# 04_DISPLAY.net
KiCad netlist of a schematic drawn in Altium Designer
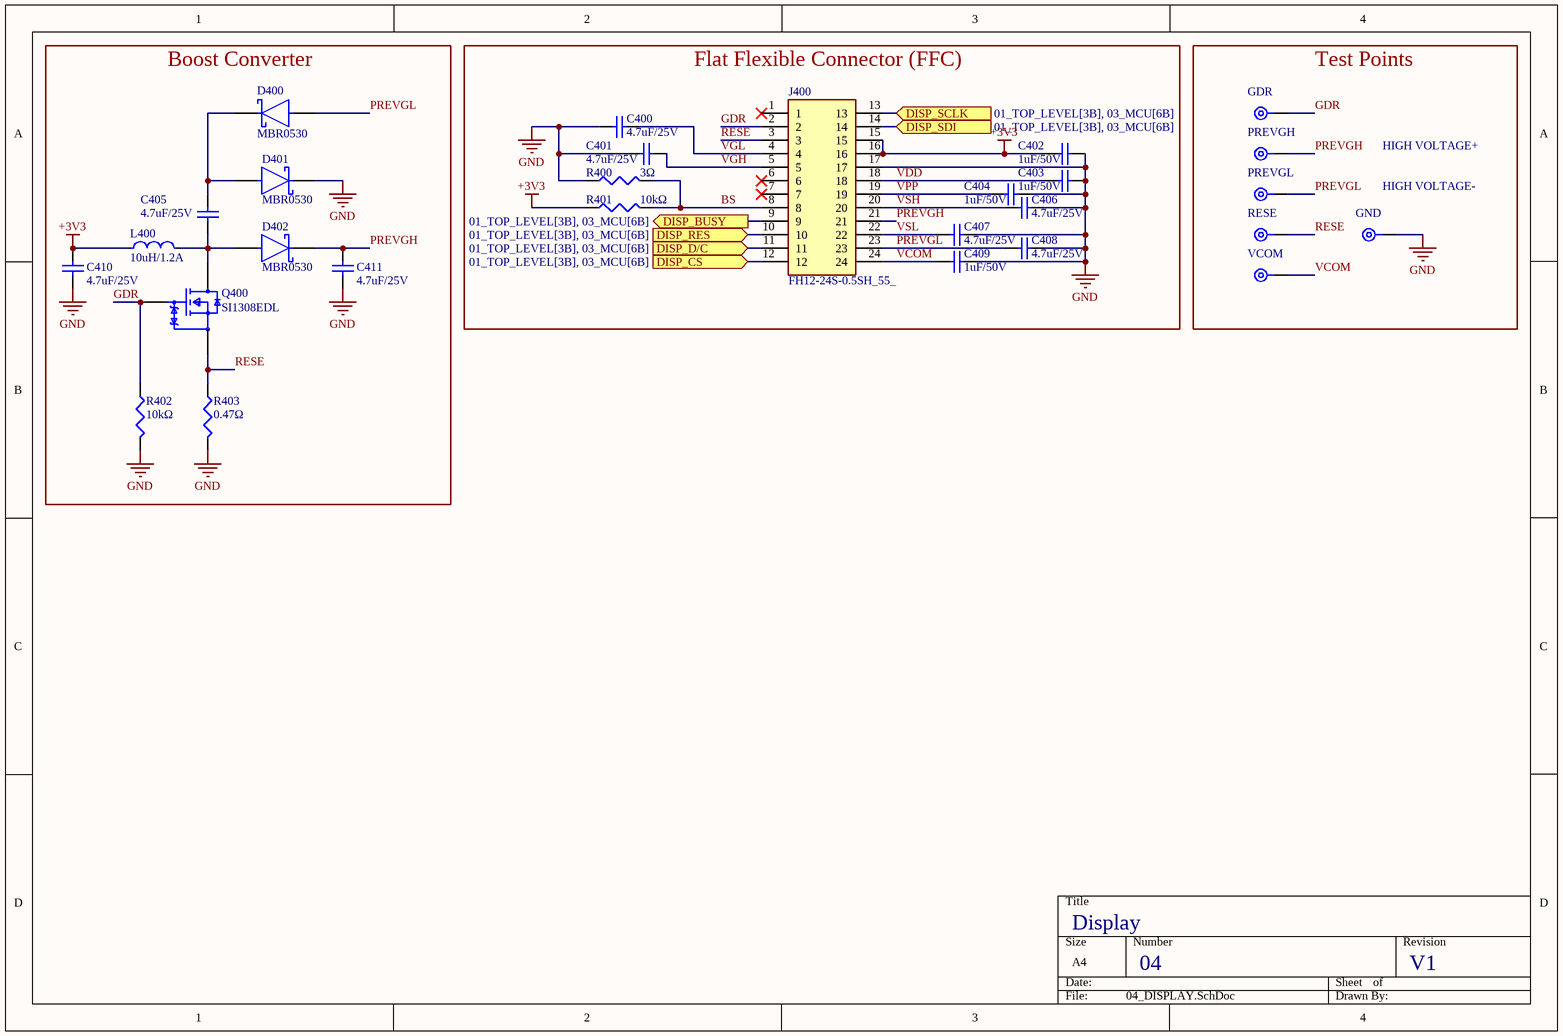
[diagram p0: 04_DISPLAY.SchDoc]

(export (version "E")
  (design (tool "Eeschema 10.0.6"))
  (components
    (comp (ref "C400")
      (value "4.7uF/25V")
      (footprint "CAPC1005X55X25LL05T10")
      (description "Chip Capacitor, 1 uF, +/- 10%, 6.3 V, 0402 (1005 Metric)")
      (fields (field (name "TOLERANCE") "10%") (field (name "Comment") "Capacitor 1 uF +/- 10% 6.3 V 0402"))
      (libsource (lib "CPRT Workspace") (part "CAP-NP-2"))
    )
    (comp (ref "C401")
      (value "4.7uF/25V")
      (footprint "CAPC1005X55X25LL05T10")
      (description "Chip Capacitor, 1 uF, +/- 10%, 6.3 V, 0402 (1005 Metric)")
      (fields (field (name "TOLERANCE") "10%") (field (name "Comment") "Capacitor 1 uF +/- 10% 6.3 V 0402"))
      (libsource (lib "CPRT Workspace") (part "CAP-NP-2"))
    )
    (comp (ref "C402")
      (value "1uF/50V")
      (footprint "CAPC1005X55X25LL05T10")
      (description "Chip Capacitor, 1 uF, +/- 10%, 6.3 V, 0402 (1005 Metric)")
      (fields (field (name "TOLERANCE") "10%") (field (name "Comment") "Capacitor 1 uF +/- 10% 6.3 V 0402"))
      (libsource (lib "CPRT Workspace") (part "CAP-NP-2"))
    )
    (comp (ref "C403")
      (value "1uF/50V")
      (footprint "CAPC1005X55X25LL05T10")
      (description "Chip Capacitor, 1 uF, +/- 10%, 6.3 V, 0402 (1005 Metric)")
      (fields (field (name "TOLERANCE") "10%") (field (name "Comment") "Capacitor 1 uF +/- 10% 6.3 V 0402"))
      (libsource (lib "CPRT Workspace") (part "CAP-NP-2"))
    )
    (comp (ref "C404")
      (value "1uF/50V")
      (footprint "CAPC1005X55X25LL05T10")
      (description "Chip Capacitor, 1 uF, +/- 10%, 6.3 V, 0402 (1005 Metric)")
      (fields (field (name "TOLERANCE") "10%") (field (name "Comment") "Capacitor 1 uF +/- 10% 6.3 V 0402"))
      (libsource (lib "CPRT Workspace") (part "CAP-NP-2"))
    )
    (comp (ref "C405")
      (value "4.7uF/25V")
      (footprint "CAPC1005X55X25LL05T10")
      (description "Chip Capacitor, 1 uF, +/- 10%, 6.3 V, 0402 (1005 Metric)")
      (fields (field (name "TOLERANCE") "10%") (field (name "Comment") "Capacitor 1 uF +/- 10% 6.3 V 0402"))
      (libsource (lib "CPRT Workspace") (part "CAP-NP-2"))
    )
    (comp (ref "C406")
      (value "4.7uF/25V")
      (footprint "CAPC1005X55X25LL05T10")
      (description "Chip Capacitor, 1 uF, +/- 10%, 6.3 V, 0402 (1005 Metric)")
      (fields (field (name "TOLERANCE") "10%") (field (name "Comment") "Capacitor 1 uF +/- 10% 6.3 V 0402"))
      (libsource (lib "CPRT Workspace") (part "CAP-NP-2"))
    )
    (comp (ref "C407")
      (value "4.7uF/25V")
      (footprint "CAPC1005X55X25LL05T10")
      (description "Chip Capacitor, 1 uF, +/- 10%, 6.3 V, 0402 (1005 Metric)")
      (fields (field (name "TOLERANCE") "10%") (field (name "Comment") "Capacitor 1 uF +/- 10% 6.3 V 0402"))
      (libsource (lib "CPRT Workspace") (part "CAP-NP-2"))
    )
    (comp (ref "C408")
      (value "4.7uF/25V")
      (footprint "CAPC1005X55X25LL05T10")
      (description "Chip Capacitor, 1 uF, +/- 10%, 6.3 V, 0402 (1005 Metric)")
      (fields (field (name "TOLERANCE") "10%") (field (name "Comment") "Capacitor 1 uF +/- 10% 6.3 V 0402"))
      (libsource (lib "CPRT Workspace") (part "CAP-NP-2"))
    )
    (comp (ref "C409")
      (value "1uF/50V")
      (footprint "CAPC1005X55X25LL05T10")
      (description "Chip Capacitor, 1 uF, +/- 10%, 6.3 V, 0402 (1005 Metric)")
      (fields (field (name "TOLERANCE") "10%") (field (name "Comment") "Capacitor 1 uF +/- 10% 6.3 V 0402"))
      (libsource (lib "CPRT Workspace") (part "CAP-NP-2"))
    )
    (comp (ref "C410")
      (value "4.7uF/25V")
      (footprint "CAPC1005X55X25LL05T10")
      (description "Chip Capacitor, 1 uF, +/- 10%, 6.3 V, 0402 (1005 Metric)")
      (fields (field (name "TOLERANCE") "10%") (field (name "Comment") "Capacitor 1 uF +/- 10% 6.3 V 0402"))
      (libsource (lib "CPRT Workspace") (part "CAP-NP-2"))
    )
    (comp (ref "C411")
      (value "4.7uF/25V")
      (footprint "CAPC1005X55X25LL05T10")
      (description "Chip Capacitor, 1 uF, +/- 10%, 6.3 V, 0402 (1005 Metric)")
      (fields (field (name "TOLERANCE") "10%") (field (name "Comment") "Capacitor 1 uF +/- 10% 6.3 V 0402"))
      (libsource (lib "CPRT Workspace") (part "CAP-NP-2"))
    )
    (comp (ref "D400")
      (value "MBR0530")
      (footprint "FP-425-04-MFG")
      (description "DIODE SCHOTTKY 30V 500MA SOD123")
      (libsource (lib "Altium Content Vault") (part "1d6ec82d83fb6aee721767c19dac4b9"))
    )
    (comp (ref "D401")
      (value "MBR0530")
      (footprint "FP-425-04-MFG")
      (description "DIODE SCHOTTKY 30V 500MA SOD123")
      (libsource (lib "Altium Content Vault") (part "1d6ec82d83fb6aee721767c19dac4b9"))
    )
    (comp (ref "D402")
      (value "MBR0530")
      (footprint "FP-425-04-MFG")
      (description "DIODE SCHOTTKY 30V 500MA SOD123")
      (libsource (lib "Altium Content Vault") (part "1d6ec82d83fb6aee721767c19dac4b9"))
    )
    (comp (ref "GDR")
      (value "TPAD10R")
      (footprint "TEST_POINT")
      (description "Testpont Pad 10R")
      (libsource (lib "Schlib1") (part "TEST_POINT"))
    )
    (comp (ref "GND")
      (value "TPAD10R")
      (footprint "TEST_POINT")
      (description "Testpont Pad 10R")
      (libsource (lib "Schlib1") (part "TEST_POINT"))
    )
    (comp (ref "J400")
      (value "FH12-24S-0.5SH_55_")
      (footprint "FH12-24S-0.5SH(55)")
      (description "Connector")
      (fields
        (field (name "MANUFACTURER_PART_NUMBER") "FH12-24S-0.5SH(55)")
        (field (name "MOUSER PART NUMBER") "798-FH12-24S-0.5SH55")
      )
      (libsource (lib "Schlib1") (part "FH12-24S-0.5SH_55_"))
    )
    (comp (ref "L400")
      (value "10uH/1.2A")
      (footprint "FP-LQH5BPB_T0-MFG")
      (description "Wire Wound Ferrite Inductor for Power Lines 10μH ±20% 0.1272Ω 1.60A 2020")
      (fields (field (name "TOLERANCE") "20%"))
      (libsource (lib "Altium Content Vault") (part "725321dda6339637d4d059423bc1c3c"))
    )
    (comp (ref "PREVGH")
      (value "TPAD10R")
      (footprint "TEST_POINT")
      (description "Testpont Pad 10R")
      (libsource (lib "Schlib1") (part "TEST_POINT"))
    )
    (comp (ref "PREVGL")
      (value "TPAD10R")
      (footprint "TEST_POINT")
      (description "Testpont Pad 10R")
      (libsource (lib "Schlib1") (part "TEST_POINT"))
    )
    (comp (ref "Q400")
      (value "SI1308EDL")
      (footprint "FP-5549-MFG")
      (description "MOSFET N-CH 30V 1.4A SC-70-3")
      (libsource (lib "Altium Content Vault") (part "e96677422f20f20903245877d22b385"))
    )
    (comp (ref "R400")
      (value "3Ω")
      (footprint "RESC0402(1005)_L")
      (description "100R 0.063W 1% 0402 (1005 Metric)  SMD")
      (fields (field (name "TOLERANCE") "1%") (field (name "POWER") "63mW"))
      (libsource (lib "CPRT Workspace") (part "100R2F"))
    )
    (comp (ref "R401")
      (value "10kΩ")
      (footprint "RESC0402(1005)_L")
      (description "100R 0.063W 1% 0402 (1005 Metric)  SMD")
      (fields (field (name "TOLERANCE") "1%") (field (name "POWER") "63mW"))
      (libsource (lib "CPRT Workspace") (part "100R2F"))
    )
    (comp (ref "R402")
      (value "10kΩ")
      (footprint "RESC0402(1005)_L")
      (description "100R 0.063W 1% 0402 (1005 Metric)  SMD")
      (fields (field (name "TOLERANCE") "1%") (field (name "POWER") "63mW"))
      (libsource (lib "CPRT Workspace") (part "100R2F"))
    )
    (comp (ref "R403")
      (value "0.47Ω")
      (footprint "RESC0402(1005)_L")
      (description "100R 0.063W 1% 0402 (1005 Metric)  SMD")
      (fields (field (name "TOLERANCE") "1%") (field (name "POWER") "63mW"))
      (libsource (lib "CPRT Workspace") (part "100R2F"))
    )
    (comp (ref "RESE")
      (value "TPAD10R")
      (footprint "TEST_POINT")
      (description "Testpont Pad 10R")
      (libsource (lib "Schlib1") (part "TEST_POINT"))
    )
    (comp (ref "VCOM")
      (value "TPAD10R")
      (footprint "TEST_POINT")
      (description "Testpont Pad 10R")
      (libsource (lib "Schlib1") (part "TEST_POINT"))
    )
  )
  (nets
    (net (code "1") (name "+3V3") (class "Default")
      (node (ref "C402") (pin "2") (pinfunction "2_2") (pintype "passive"))
      (node (ref "C410") (pin "2") (pinfunction "2_2") (pintype "passive"))
      (node (ref "J400") (pin "15") (pinfunction "15_15") (pintype "passive"))
      (node (ref "J400") (pin "16") (pinfunction "16_16") (pintype "passive"))
      (node (ref "L400") (pin "1") (pinfunction "1_1") (pintype "passive"))
      (node (ref "R401") (pin "1") (pinfunction "1_1") (pintype "passive"))
    )
    (net (code "2") (name "/BS") (class "Default")
      (node (ref "J400") (pin "8") (pinfunction "8_8") (pintype "passive"))
      (node (ref "R400") (pin "2") (pinfunction "2_2") (pintype "passive"))
      (node (ref "R401") (pin "2") (pinfunction "2_2") (pintype "passive"))
    )
    (net (code "3") (name "/DISP_BUSY") (class "Default")
      (node (ref "J400") (pin "9") (pinfunction "9_9") (pintype "passive"))
    )
    (net (code "4") (name "/DISP_CS") (class "Default")
      (node (ref "J400") (pin "12") (pinfunction "12_12") (pintype "passive"))
    )
    (net (code "5") (name "/DISP_D{slash}C") (class "Default")
      (node (ref "J400") (pin "11") (pinfunction "11_11") (pintype "passive"))
    )
    (net (code "6") (name "/DISP_RES") (class "Default")
      (node (ref "J400") (pin "10") (pinfunction "10_10") (pintype "passive"))
    )
    (net (code "7") (name "/DISP_SCLK") (class "Default")
      (node (ref "J400") (pin "13") (pinfunction "13_13") (pintype "passive"))
    )
    (net (code "8") (name "/DISP_SDI") (class "Default")
      (node (ref "J400") (pin "14") (pinfunction "14_14") (pintype "passive"))
    )
    (net (code "9") (name "/GDR") (class "Default")
      (node (ref "GDR") (pin "1") (pinfunction "1_1") (pintype "passive"))
      (node (ref "J400") (pin "2") (pinfunction "2_2") (pintype "passive"))
      (node (ref "Q400") (pin "1") (pinfunction "G_1") (pintype "passive"))
      (node (ref "R402") (pin "1") (pinfunction "1_1") (pintype "passive"))
    )
    (net (code "10") (name "/PREVGH") (class "Default")
      (node (ref "C411") (pin "2") (pinfunction "2_2") (pintype "passive"))
      (node (ref "D402") (pin "1") (pinfunction "C_1") (pintype "passive"))
      (node (ref "J400") (pin "21") (pinfunction "21_21") (pintype "passive"))
      (node (ref "PREVGH") (pin "1") (pinfunction "1_1") (pintype "passive"))
    )
    (net (code "11") (name "/PREVGL") (class "Default")
      (node (ref "C408") (pin "2") (pinfunction "2_2") (pintype "passive"))
      (node (ref "D400") (pin "2") (pinfunction "A_2") (pintype "passive"))
      (node (ref "J400") (pin "23") (pinfunction "23_23") (pintype "passive"))
      (node (ref "PREVGL") (pin "1") (pinfunction "1_1") (pintype "passive"))
    )
    (net (code "12") (name "/RESE") (class "Default")
      (node (ref "J400") (pin "3") (pinfunction "3_3") (pintype "passive"))
      (node (ref "Q400") (pin "2") (pinfunction "S_2") (pintype "passive"))
      (node (ref "R403") (pin "1") (pinfunction "1_1") (pintype "passive"))
      (node (ref "RESE") (pin "1") (pinfunction "1_1") (pintype "passive"))
    )
    (net (code "13") (name "/VCOM") (class "Default")
      (node (ref "C409") (pin "2") (pinfunction "2_2") (pintype "passive"))
      (node (ref "J400") (pin "24") (pinfunction "24_24") (pintype "passive"))
      (node (ref "VCOM") (pin "1") (pinfunction "1_1") (pintype "passive"))
    )
    (net (code "14") (name "/VDD") (class "Default")
      (node (ref "C403") (pin "2") (pinfunction "2_2") (pintype "passive"))
      (node (ref "J400") (pin "18") (pinfunction "18_18") (pintype "passive"))
    )
    (net (code "15") (name "/VGH") (class "Default")
      (node (ref "C401") (pin "1") (pinfunction "1_1") (pintype "passive"))
      (node (ref "J400") (pin "5") (pinfunction "5_5") (pintype "passive"))
    )
    (net (code "16") (name "/VGL") (class "Default")
      (node (ref "C400") (pin "1") (pinfunction "1_1") (pintype "passive"))
      (node (ref "J400") (pin "4") (pinfunction "4_4") (pintype "passive"))
    )
    (net (code "17") (name "/VPP") (class "Default")
      (node (ref "C404") (pin "2") (pinfunction "2_2") (pintype "passive"))
      (node (ref "J400") (pin "19") (pinfunction "19_19") (pintype "passive"))
    )
    (net (code "18") (name "/VSH") (class "Default")
      (node (ref "C406") (pin "2") (pinfunction "2_2") (pintype "passive"))
      (node (ref "J400") (pin "20") (pinfunction "20_20") (pintype "passive"))
    )
    (net (code "19") (name "/VSL") (class "Default")
      (node (ref "C407") (pin "2") (pinfunction "2_2") (pintype "passive"))
      (node (ref "J400") (pin "22") (pinfunction "22_22") (pintype "passive"))
    )
    (net (code "20") (name "GND") (class "Default")
      (node (ref "C400") (pin "2") (pinfunction "2_2") (pintype "passive"))
      (node (ref "C401") (pin "2") (pinfunction "2_2") (pintype "passive"))
      (node (ref "C402") (pin "1") (pinfunction "1_1") (pintype "passive"))
      (node (ref "C403") (pin "1") (pinfunction "1_1") (pintype "passive"))
      (node (ref "C404") (pin "1") (pinfunction "1_1") (pintype "passive"))
      (node (ref "C406") (pin "1") (pinfunction "1_1") (pintype "passive"))
      (node (ref "C407") (pin "1") (pinfunction "1_1") (pintype "passive"))
      (node (ref "C408") (pin "1") (pinfunction "1_1") (pintype "passive"))
      (node (ref "C409") (pin "1") (pinfunction "1_1") (pintype "passive"))
      (node (ref "C410") (pin "1") (pinfunction "1_1") (pintype "passive"))
      (node (ref "C411") (pin "1") (pinfunction "1_1") (pintype "passive"))
      (node (ref "D401") (pin "1") (pinfunction "C_1") (pintype "passive"))
      (node (ref "GND") (pin "1") (pinfunction "1_1") (pintype "passive"))
      (node (ref "J400") (pin "17") (pinfunction "17_17") (pintype "passive"))
      (node (ref "R400") (pin "1") (pinfunction "1_1") (pintype "passive"))
      (node (ref "R402") (pin "2") (pinfunction "2_2") (pintype "passive"))
      (node (ref "R403") (pin "2") (pinfunction "2_2") (pintype "passive"))
    )
    (net (code "21") (name "Net-(D400-C)") (class "Default")
      (node (ref "C405") (pin "2") (pinfunction "2_2") (pintype "passive"))
      (node (ref "D400") (pin "1") (pinfunction "C_1") (pintype "passive"))
      (node (ref "D401") (pin "2") (pinfunction "A_2") (pintype "passive"))
    )
    (net (code "22") (name "Net-(D402-A)") (class "Default")
      (node (ref "C405") (pin "1") (pinfunction "1_1") (pintype "passive"))
      (node (ref "D402") (pin "2") (pinfunction "A_2") (pintype "passive"))
      (node (ref "L400") (pin "2") (pinfunction "2_2") (pintype "passive"))
      (node (ref "Q400") (pin "3") (pinfunction "D_3") (pintype "passive"))
    )
    (net (code "23") (name "unconnected-(J400-Pad1)") (class "Default")
      (node (ref "J400") (pin "1") (pinfunction "1_1") (pintype "passive+no_connect"))
    )
    (net (code "24") (name "unconnected-(J400-Pad6)") (class "Default")
      (node (ref "J400") (pin "6") (pinfunction "6_6") (pintype "passive+no_connect"))
    )
    (net (code "25") (name "unconnected-(J400-Pad7)") (class "Default")
      (node (ref "J400") (pin "7") (pinfunction "7_7") (pintype "passive+no_connect"))
    )
  )
)
